# Stepper_Motor1.net
KiCad netlist of a schematic drawn in Altium Designer
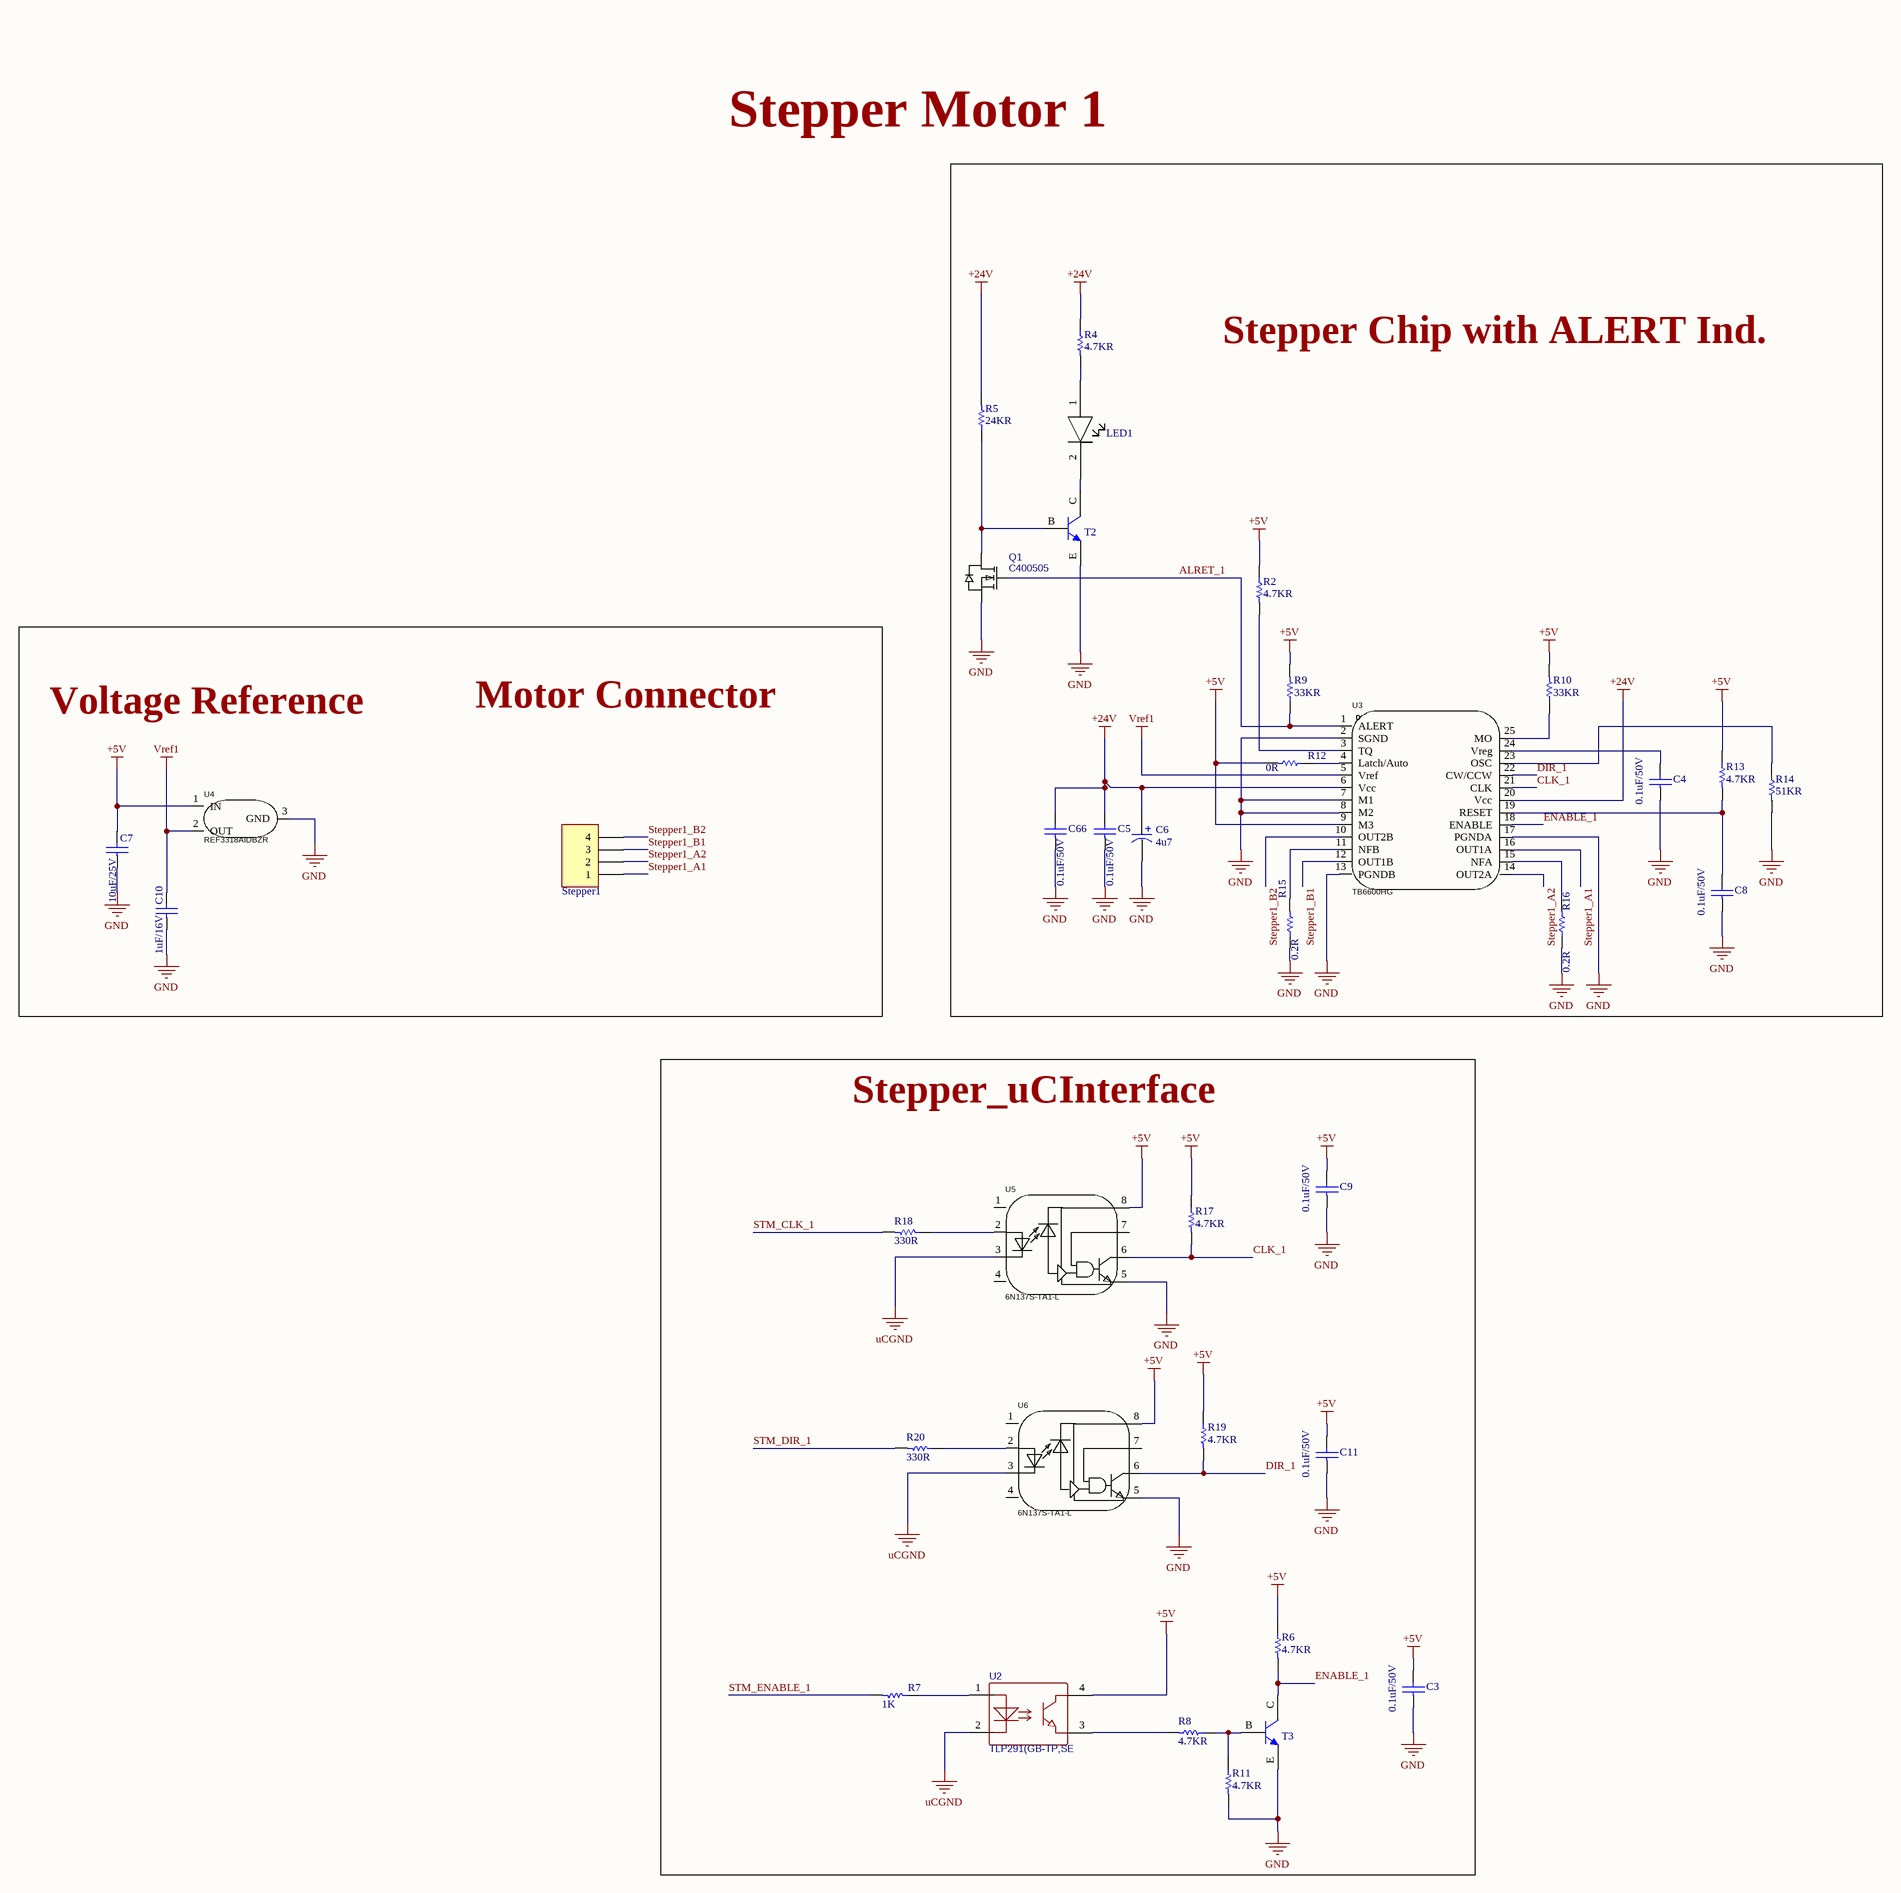
[diagram p0: Stepper Motor1.SchDoc]

(export (version "E")
  (design (tool "Eeschema 10.0.6"))
  (components
    (comp (ref "C3")
      (value "0.1uF/50V")
      (footprint "PCBComponent_1")
      (description "C1591")
      (fields (field (name "CREATED BY") "NourAldin"))
      (libsource (lib "0603 Capacitor") (part "0603 Capacitor"))
    )
    (comp (ref "C4")
      (value "0.1uF/50V")
      (footprint "PCBComponent_1")
      (description "C1591")
      (fields (field (name "CREATED BY") "NourAldin"))
      (libsource (lib "0603 Capacitor") (part "0603 Capacitor"))
    )
    (comp (ref "C5")
      (value "0.1uF/50V")
      (footprint "PCBComponent_1")
      (description "C1591")
      (fields (field (name "CREATED BY") "NourAldin"))
      (libsource (lib "0603 Capacitor") (part "0603 Capacitor"))
    )
    (comp (ref "C6")
      (value "4u7")
      (footprint "CAPLEAD_D6.3mm")
      (description "C2691843")
      (fields
        (field (name "MANUFACTURER") "KEMET")
        (field (name "MANUFACTURER PART NUMBER") "A759EQ475M2AAAE160")
      )
      (libsource (lib "GlobalLib") (part "A759EQ475M2AAAE160"))
    )
    (comp (ref "C7")
      (value "10uF/25V")
      (footprint "PCBComponent_1")
      (description "C96446")
      (fields (field (name "CREATED BY") "NourAldin"))
      (libsource (lib "0603 Capacitor") (part "0603 Capacitor"))
    )
    (comp (ref "C8")
      (value "0.1uF/50V")
      (footprint "PCBComponent_1")
      (description "C1591")
      (fields (field (name "CREATED BY") "NourAldin"))
      (libsource (lib "0603 Capacitor") (part "0603 Capacitor"))
    )
    (comp (ref "C9")
      (value "0.1uF/50V")
      (footprint "PCBComponent_1")
      (description "C1591")
      (fields (field (name "CREATED BY") "NourAldin"))
      (libsource (lib "0603 Capacitor") (part "0603 Capacitor"))
    )
    (comp (ref "C10")
      (value "1uF/16V")
      (footprint "PCBComponent_1")
      (description "C1592")
      (fields (field (name "CREATED BY") "NourAldin"))
      (libsource (lib "0603 Capacitor") (part "0603 Capacitor"))
    )
    (comp (ref "C11")
      (value "0.1uF/50V")
      (footprint "PCBComponent_1")
      (description "C1591")
      (fields (field (name "CREATED BY") "NourAldin"))
      (libsource (lib "0603 Capacitor") (part "0603 Capacitor"))
    )
    (comp (ref "C66")
      (value "0.1uF/50V")
      (footprint "PCBComponent_1")
      (description "C1591")
      (fields (field (name "CREATED BY") "NourAldin"))
      (libsource (lib "0603 Capacitor") (part "0603 Capacitor"))
    )
    (comp (ref "LED1")
      (value "1206 LED")
      (footprint "1206 LED")
      (description "C434438")
      (fields (field (name "CREATED BY") "NourAldin"))
      (libsource (lib "1206 LED") (part "1206 LED"))
    )
    (comp (ref "Q1")
      (value "C400505")
      (footprint "SOT-23-3_L2.9-W1.3-P1.90-LS2.4-BR")
      (fields
        (field (name "MANUFACTURER") "YANGJIE(扬杰)")
        (field (name "MANUFACTURER PART") "BSS138")
        (field (name "CONTRIBUTOR") "LCSC")
      )
      (libsource (lib "DIVERSE") (part "BSS138_MOSFET"))
    )
    (comp (ref "R2")
      (value "4.7KR")
      (footprint "R0402")
      (description "C105871")
      (libsource (lib "DIVERSE") (part "0402 Resistor"))
    )
    (comp (ref "R4")
      (value "4.7KR")
      (footprint "R0402")
      (description "C105871")
      (libsource (lib "DIVERSE") (part "0402 Resistor"))
    )
    (comp (ref "R5")
      (value "24KR")
      (footprint "RESC1608X06N")
      (description "C2930081")
      (fields (field (name "CREATED BY") "NourAldin"))
      (libsource (lib "0603 Resistor") (part "0603 Resistor"))
    )
    (comp (ref "R6")
      (value "4.7KR")
      (footprint "R0402")
      (description "C105871")
      (libsource (lib "DIVERSE") (part "0402 Resistor"))
    )
    (comp (ref "R7")
      (value "1K")
      (footprint "R0402")
      (description "C106235")
      (libsource (lib "DIVERSE") (part "0402 Resistor"))
    )
    (comp (ref "R8")
      (value "4.7KR")
      (footprint "R0402")
      (description "C105871")
      (libsource (lib "DIVERSE") (part "0402 Resistor"))
    )
    (comp (ref "R9")
      (value "33KR")
      (footprint "RESC1608X06N")
      (description "C126359")
      (fields (field (name "CREATED BY") "NourAldin"))
      (libsource (lib "0603 Resistor") (part "0603 Resistor"))
    )
    (comp (ref "R10")
      (value "33KR")
      (footprint "RESC1608X06N")
      (description "C126359")
      (fields (field (name "CREATED BY") "NourAldin"))
      (libsource (lib "0603 Resistor") (part "0603 Resistor"))
    )
    (comp (ref "R11")
      (value "4.7KR")
      (footprint "R0402")
      (description "C105871")
      (libsource (lib "DIVERSE") (part "0402 Resistor"))
    )
    (comp (ref "R12")
      (value "0R")
      (footprint "RESC1608X06N")
      (description "C100044")
      (fields (field (name "CREATED BY") "NourAldin"))
      (libsource (lib "0603 Resistor") (part "0603 Resistor"))
    )
    (comp (ref "R13")
      (value "4.7KR")
      (footprint "R0402")
      (description "C105871")
      (libsource (lib "DIVERSE") (part "0402 Resistor"))
    )
    (comp (ref "R14")
      (value "51KR")
      (footprint "R0402")
      (description "C107230")
      (libsource (lib "DIVERSE") (part "0402 Resistor"))
    )
    (comp (ref "R15")
      (value "0.2R")
      (footprint "RESC6431X12N")
      (description "C2903473")
      (fields (field (name "CREATED BY") "NourAldin"))
      (libsource (lib "2512 Resistor") (part "2512 Resistor"))
    )
    (comp (ref "R16")
      (value "0.2R")
      (footprint "RESC6431X12N")
      (description "C2903473")
      (fields (field (name "CREATED BY") "NourAldin"))
      (libsource (lib "2512 Resistor") (part "2512 Resistor"))
    )
    (comp (ref "R17")
      (value "4.7KR")
      (footprint "R0402")
      (description "C105871")
      (libsource (lib "DIVERSE") (part "0402 Resistor"))
    )
    (comp (ref "R18")
      (value "330R")
      (footprint "R0402")
      (description "C105875")
      (libsource (lib "DIVERSE") (part "0402 Resistor"))
    )
    (comp (ref "R19")
      (value "4.7KR")
      (footprint "R0402")
      (description "C105871")
      (libsource (lib "DIVERSE") (part "0402 Resistor"))
    )
    (comp (ref "R20")
      (value "330R")
      (footprint "R0402")
      (description "C105875")
      (libsource (lib "DIVERSE") (part "0402 Resistor"))
    )
    (comp (ref "Stepper1")
      (value "Header 4 Pin Polar")
      (footprint "PCBComponent_1")
      (description "C144395")
      (libsource (lib "Header 4 Pin Polar") (part "Header 4 Pin Polar"))
    )
    (comp (ref "T2")
      (value "MMBT3904 Transistor")
      (footprint "MMBT3904")
      (description "C108429")
      (fields (field (name "CREATED BY") "NourAldin"))
      (libsource (lib "MMBT3904 Transistor") (part "MMBT3904 Transistor"))
    )
    (comp (ref "T3")
      (value "MMBT3904 Transistor")
      (footprint "MMBT3904")
      (description "C108429")
      (fields (field (name "CREATED BY") "NourAldin"))
      (libsource (lib "MMBT3904 Transistor") (part "MMBT3904 Transistor"))
    )
    (comp (ref "U2")
      (value "TLP291(GB-TP,SE")
      (footprint "SOP-4-1.27mm")
      (description "C55144")
      (libsource (lib "CO2_Lib") (part "TLP291(GB-TP,SE(T"))
    )
    (comp (ref "U3")
      (value "TB6600HG")
      (footprint "HZIP25-P-1.0_TB6600HG - HEATSINK")
      (description "C66042")
      (fields (field (name "MANUFACTURER") "TOSHIBA(东芝)"))
      (libsource (lib "LIB") (part "TB6600HG"))
    )
    (comp (ref "U4")
      (value "REF3318AIDBZR")
      (footprint "SOT-23-3_L2.9-W1.3-P1.90-LS2.4-BR")
      (description "C115877")
      (fields (field (name "MANUFACTURER") "TI(德州仪器)") (field (name "TOLERANCE") "±0.15%"))
      (libsource (lib "LIB") (part "REF3318AIDBZR"))
    )
    (comp (ref "U5")
      (value "6N137S-TA1-L")
      (footprint "SOP-8_L9.8-W6.6-P2.54-LS10.3-BL")
      (description "C92651")
      (fields (field (name "MANUFACTURER") "LITEON(光宝)"))
      (libsource (lib "LIB") (part "6N137S-TA1-L"))
    )
    (comp (ref "U6")
      (value "6N137S-TA1-L")
      (footprint "SOP-8_L9.8-W6.6-P2.54-LS10.3-BL")
      (description "C92651")
      (fields (field (name "MANUFACTURER") "LITEON(光宝)"))
      (libsource (lib "LIB") (part "6N137S-TA1-L"))
    )
  )
  (nets
    (net (code "1") (name "+5V") (class "Default")
      (node (ref "C11") (pin "2") (pinfunction "2_2") (pintype "passive"))
      (node (ref "C3") (pin "2") (pinfunction "2_2") (pintype "passive"))
      (node (ref "C7") (pin "2") (pinfunction "2_2") (pintype "passive"))
      (node (ref "C9") (pin "2") (pinfunction "2_2") (pintype "passive"))
      (node (ref "R10") (pin "2") (pinfunction "2_2") (pintype "passive"))
      (node (ref "R12") (pin "2") (pinfunction "2_2") (pintype "passive"))
      (node (ref "R13") (pin "1") (pinfunction "1_1") (pintype "passive"))
      (node (ref "R17") (pin "1") (pinfunction "1_1") (pintype "passive"))
      (node (ref "R19") (pin "1") (pinfunction "1_1") (pintype "passive"))
      (node (ref "R2") (pin "1") (pinfunction "1_1") (pintype "passive"))
      (node (ref "R6") (pin "1") (pinfunction "1_1") (pintype "passive"))
      (node (ref "R9") (pin "2") (pinfunction "2_2") (pintype "passive"))
      (node (ref "U2") (pin "4") (pinfunction "4_4") (pintype "passive"))
      (node (ref "U3") (pin "9") (pinfunction "M3_9") (pintype "passive"))
      (node (ref "U4") (pin "1") (pinfunction "IN_1") (pintype "passive"))
      (node (ref "U5") (pin "8") (pinfunction "8_8") (pintype "passive"))
      (node (ref "U6") (pin "8") (pinfunction "8_8") (pintype "passive"))
    )
    (net (code "2") (name "+24V") (class "Default")
      (node (ref "C5") (pin "2") (pinfunction "2_2") (pintype "passive"))
      (node (ref "C6") (pin "1") (pinfunction "1_1") (pintype "passive"))
      (node (ref "C66") (pin "2") (pinfunction "2_2") (pintype "passive"))
      (node (ref "R4") (pin "1") (pinfunction "1_1") (pintype "passive"))
      (node (ref "R5") (pin "2") (pinfunction "2_2") (pintype "passive"))
      (node (ref "U3") (pin "20") (pinfunction "Vcc_20") (pintype "passive"))
      (node (ref "U3") (pin "6") (pinfunction "Vcc_6") (pintype "passive"))
    )
    (net (code "3") (name "/ALRET_1") (class "Default")
      (node (ref "Q1") (pin "1") (pinfunction "G_1") (pintype "passive"))
      (node (ref "R9") (pin "1") (pinfunction "1_1") (pintype "passive"))
      (node (ref "U3") (pin "1") (pinfunction "ALERT_1") (pintype "passive"))
    )
    (net (code "4") (name "/CLK_1") (class "Default")
      (node (ref "R17") (pin "2") (pinfunction "2_2") (pintype "passive"))
      (node (ref "U3") (pin "21") (pinfunction "CLK_21") (pintype "passive"))
      (node (ref "U5") (pin "6") (pinfunction "6_6") (pintype "passive"))
    )
    (net (code "5") (name "/DIR_1") (class "Default")
      (node (ref "R19") (pin "2") (pinfunction "2_2") (pintype "passive"))
      (node (ref "U3") (pin "22") (pinfunction "CW/CCW_22") (pintype "passive"))
      (node (ref "U6") (pin "6") (pinfunction "6_6") (pintype "passive"))
    )
    (net (code "6") (name "/ENABLE_1") (class "Default")
      (node (ref "R6") (pin "2") (pinfunction "2_2") (pintype "passive"))
      (node (ref "T3") (pin "C") (pinfunction "C_C") (pintype "passive"))
      (node (ref "U3") (pin "18") (pinfunction "ENABLE_18") (pintype "passive"))
    )
    (net (code "7") (name "/STM_CLK_1") (class "Default")
      (node (ref "R18") (pin "2") (pinfunction "2_2") (pintype "passive"))
    )
    (net (code "8") (name "/STM_DIR_1") (class "Default")
      (node (ref "R20") (pin "2") (pinfunction "2_2") (pintype "passive"))
    )
    (net (code "9") (name "/STM_ENABLE_1") (class "Default")
      (node (ref "R7") (pin "2") (pinfunction "2_2") (pintype "passive"))
    )
    (net (code "10") (name "/Stepper1_A1") (class "Default")
      (node (ref "Stepper1") (pin "1") (pinfunction "1_1") (pintype "passive"))
      (node (ref "U3") (pin "16") (pinfunction "OUT1A_16") (pintype "passive"))
    )
    (net (code "11") (name "/Stepper1_A2") (class "Default")
      (node (ref "Stepper1") (pin "2") (pinfunction "2_2") (pintype "passive"))
      (node (ref "U3") (pin "14") (pinfunction "OUT2A_14") (pintype "passive"))
    )
    (net (code "12") (name "/Stepper1_B1") (class "Default")
      (node (ref "Stepper1") (pin "3") (pinfunction "3_3") (pintype "passive"))
      (node (ref "U3") (pin "12") (pinfunction "OUT1B_12") (pintype "passive"))
    )
    (net (code "13") (name "/Stepper1_B2") (class "Default")
      (node (ref "Stepper1") (pin "4") (pinfunction "4_4") (pintype "passive"))
      (node (ref "U3") (pin "10") (pinfunction "OUT2B_10") (pintype "passive"))
    )
    (net (code "14") (name "GND") (class "Default")
      (node (ref "C10") (pin "1") (pinfunction "1_1") (pintype "passive"))
      (node (ref "C11") (pin "1") (pinfunction "1_1") (pintype "passive"))
      (node (ref "C3") (pin "1") (pinfunction "1_1") (pintype "passive"))
      (node (ref "C4") (pin "1") (pinfunction "1_1") (pintype "passive"))
      (node (ref "C5") (pin "1") (pinfunction "1_1") (pintype "passive"))
      (node (ref "C6") (pin "2") (pinfunction "2_2") (pintype "passive"))
      (node (ref "C66") (pin "1") (pinfunction "1_1") (pintype "passive"))
      (node (ref "C7") (pin "1") (pinfunction "1_1") (pintype "passive"))
      (node (ref "C8") (pin "1") (pinfunction "1_1") (pintype "passive"))
      (node (ref "C9") (pin "1") (pinfunction "1_1") (pintype "passive"))
      (node (ref "Q1") (pin "2") (pinfunction "S_2") (pintype "passive"))
      (node (ref "R11") (pin "2") (pinfunction "2_2") (pintype "passive"))
      (node (ref "R14") (pin "2") (pinfunction "2_2") (pintype "passive"))
      (node (ref "R15") (pin "1") (pinfunction "1_1") (pintype "passive"))
      (node (ref "R16") (pin "1") (pinfunction "1_1") (pintype "passive"))
      (node (ref "T2") (pin "E") (pinfunction "E_E") (pintype "passive"))
      (node (ref "T3") (pin "E") (pinfunction "E_E") (pintype "passive"))
      (node (ref "U3") (pin "13") (pinfunction "PGNDB_13") (pintype "passive"))
      (node (ref "U3") (pin "17") (pinfunction "PGNDA_17") (pintype "passive"))
      (node (ref "U3") (pin "2") (pinfunction "SGND_2") (pintype "passive"))
      (node (ref "U3") (pin "7") (pinfunction "M1_7") (pintype "passive"))
      (node (ref "U3") (pin "8") (pinfunction "M2_8") (pintype "passive"))
      (node (ref "U4") (pin "3") (pinfunction "GND_3") (pintype "passive"))
      (node (ref "U5") (pin "5") (pinfunction "5_5") (pintype "passive"))
      (node (ref "U6") (pin "5") (pinfunction "5_5") (pintype "passive"))
    )
    (net (code "15") (name "Net-(LED1-Pad1)") (class "Default")
      (node (ref "LED1") (pin "1") (pinfunction "1_1") (pintype "passive"))
      (node (ref "R4") (pin "2") (pinfunction "2_2") (pintype "passive"))
    )
    (net (code "16") (name "Net-(LED1-Pad2)") (class "Default")
      (node (ref "LED1") (pin "2") (pinfunction "2_2") (pintype "passive"))
      (node (ref "T2") (pin "C") (pinfunction "C_C") (pintype "passive"))
    )
    (net (code "17") (name "Net-(Q1-D)") (class "Default")
      (node (ref "Q1") (pin "3") (pinfunction "D_3") (pintype "passive"))
      (node (ref "R5") (pin "1") (pinfunction "1_1") (pintype "passive"))
      (node (ref "T2") (pin "B") (pinfunction "B_B") (pintype "passive"))
    )
    (net (code "18") (name "Net-(R7-Pad1)") (class "Default")
      (node (ref "R7") (pin "1") (pinfunction "1_1") (pintype "passive"))
      (node (ref "U2") (pin "1") (pinfunction "1_1") (pintype "passive"))
    )
    (net (code "19") (name "Net-(R8-Pad2)") (class "Default")
      (node (ref "R8") (pin "2") (pinfunction "2_2") (pintype "passive"))
      (node (ref "U2") (pin "3") (pinfunction "3_3") (pintype "passive"))
    )
    (net (code "20") (name "Net-(R11-Pad1)") (class "Default")
      (node (ref "R11") (pin "1") (pinfunction "1_1") (pintype "passive"))
      (node (ref "R8") (pin "1") (pinfunction "1_1") (pintype "passive"))
      (node (ref "T3") (pin "B") (pinfunction "B_B") (pintype "passive"))
    )
    (net (code "21") (name "Net-(R18-Pad1)") (class "Default")
      (node (ref "R18") (pin "1") (pinfunction "1_1") (pintype "passive"))
      (node (ref "U5") (pin "2") (pinfunction "2_2") (pintype "passive"))
    )
    (net (code "22") (name "Net-(R20-Pad1)") (class "Default")
      (node (ref "R20") (pin "1") (pinfunction "1_1") (pintype "passive"))
      (node (ref "U6") (pin "2") (pinfunction "2_2") (pintype "passive"))
    )
    (net (code "23") (name "Net-(U3-Latch{slash}Auto)") (class "Default")
      (node (ref "R12") (pin "1") (pinfunction "1_1") (pintype "passive"))
      (node (ref "U3") (pin "4") (pinfunction "Latch/Auto_4") (pintype "passive"))
    )
    (net (code "24") (name "Net-(U3-MO)") (class "Default")
      (node (ref "R10") (pin "1") (pinfunction "1_1") (pintype "passive"))
      (node (ref "U3") (pin "25") (pinfunction "MO_25") (pintype "passive"))
    )
    (net (code "25") (name "Net-(U3-NFA)") (class "Default")
      (node (ref "R16") (pin "2") (pinfunction "2_2") (pintype "passive"))
      (node (ref "U3") (pin "15") (pinfunction "NFA_15") (pintype "passive"))
    )
    (net (code "26") (name "Net-(U3-NFB)") (class "Default")
      (node (ref "R15") (pin "2") (pinfunction "2_2") (pintype "passive"))
      (node (ref "U3") (pin "11") (pinfunction "NFB_11") (pintype "passive"))
    )
    (net (code "27") (name "Net-(U3-OSC)") (class "Default")
      (node (ref "R14") (pin "1") (pinfunction "1_1") (pintype "passive"))
      (node (ref "U3") (pin "23") (pinfunction "OSC_23") (pintype "passive"))
    )
    (net (code "28") (name "Net-(U3-RESET)") (class "Default")
      (node (ref "C8") (pin "2") (pinfunction "2_2") (pintype "passive"))
      (node (ref "R13") (pin "2") (pinfunction "2_2") (pintype "passive"))
      (node (ref "U3") (pin "19") (pinfunction "RESET_19") (pintype "passive"))
    )
    (net (code "29") (name "Net-(U3-TQ)") (class "Default")
      (node (ref "R2") (pin "2") (pinfunction "2_2") (pintype "passive"))
      (node (ref "U3") (pin "3") (pinfunction "TQ_3") (pintype "passive"))
    )
    (net (code "30") (name "Net-(U3-Vreg)") (class "Default")
      (node (ref "C4") (pin "2") (pinfunction "2_2") (pintype "passive"))
      (node (ref "U3") (pin "24") (pinfunction "Vreg_24") (pintype "passive"))
    )
    (net (code "31") (name "Vref1") (class "Default")
      (node (ref "C10") (pin "2") (pinfunction "2_2") (pintype "passive"))
      (node (ref "U3") (pin "5") (pinfunction "Vref_5") (pintype "passive"))
      (node (ref "U4") (pin "2") (pinfunction "OUT_2") (pintype "passive"))
    )
    (net (code "32") (name "uCGND") (class "Default")
      (node (ref "U2") (pin "2") (pinfunction "2_2") (pintype "passive"))
      (node (ref "U5") (pin "3") (pinfunction "3_3") (pintype "passive"))
      (node (ref "U6") (pin "3") (pinfunction "3_3") (pintype "passive"))
    )
    (net (code "33") (name "unconnected-(U5-NC-Pad1)") (class "Default")
      (node (ref "U5") (pin "1") (pinfunction "NC_1") (pintype "passive"))
    )
    (net (code "34") (name "unconnected-(U5-NC-Pad4)") (class "Default")
      (node (ref "U5") (pin "4") (pinfunction "NC_4") (pintype "passive"))
    )
    (net (code "35") (name "unconnected-(U5-Pad7)") (class "Default")
      (node (ref "U5") (pin "7") (pinfunction "7_7") (pintype "passive"))
    )
    (net (code "36") (name "unconnected-(U6-NC-Pad1)") (class "Default")
      (node (ref "U6") (pin "1") (pinfunction "NC_1") (pintype "passive"))
    )
    (net (code "37") (name "unconnected-(U6-NC-Pad4)") (class "Default")
      (node (ref "U6") (pin "4") (pinfunction "NC_4") (pintype "passive"))
    )
    (net (code "38") (name "unconnected-(U6-Pad7)") (class "Default")
      (node (ref "U6") (pin "7") (pinfunction "7_7") (pintype "passive"))
    )
  )
)
